# MCU.net
KiCad netlist of a schematic drawn in Altium Designer
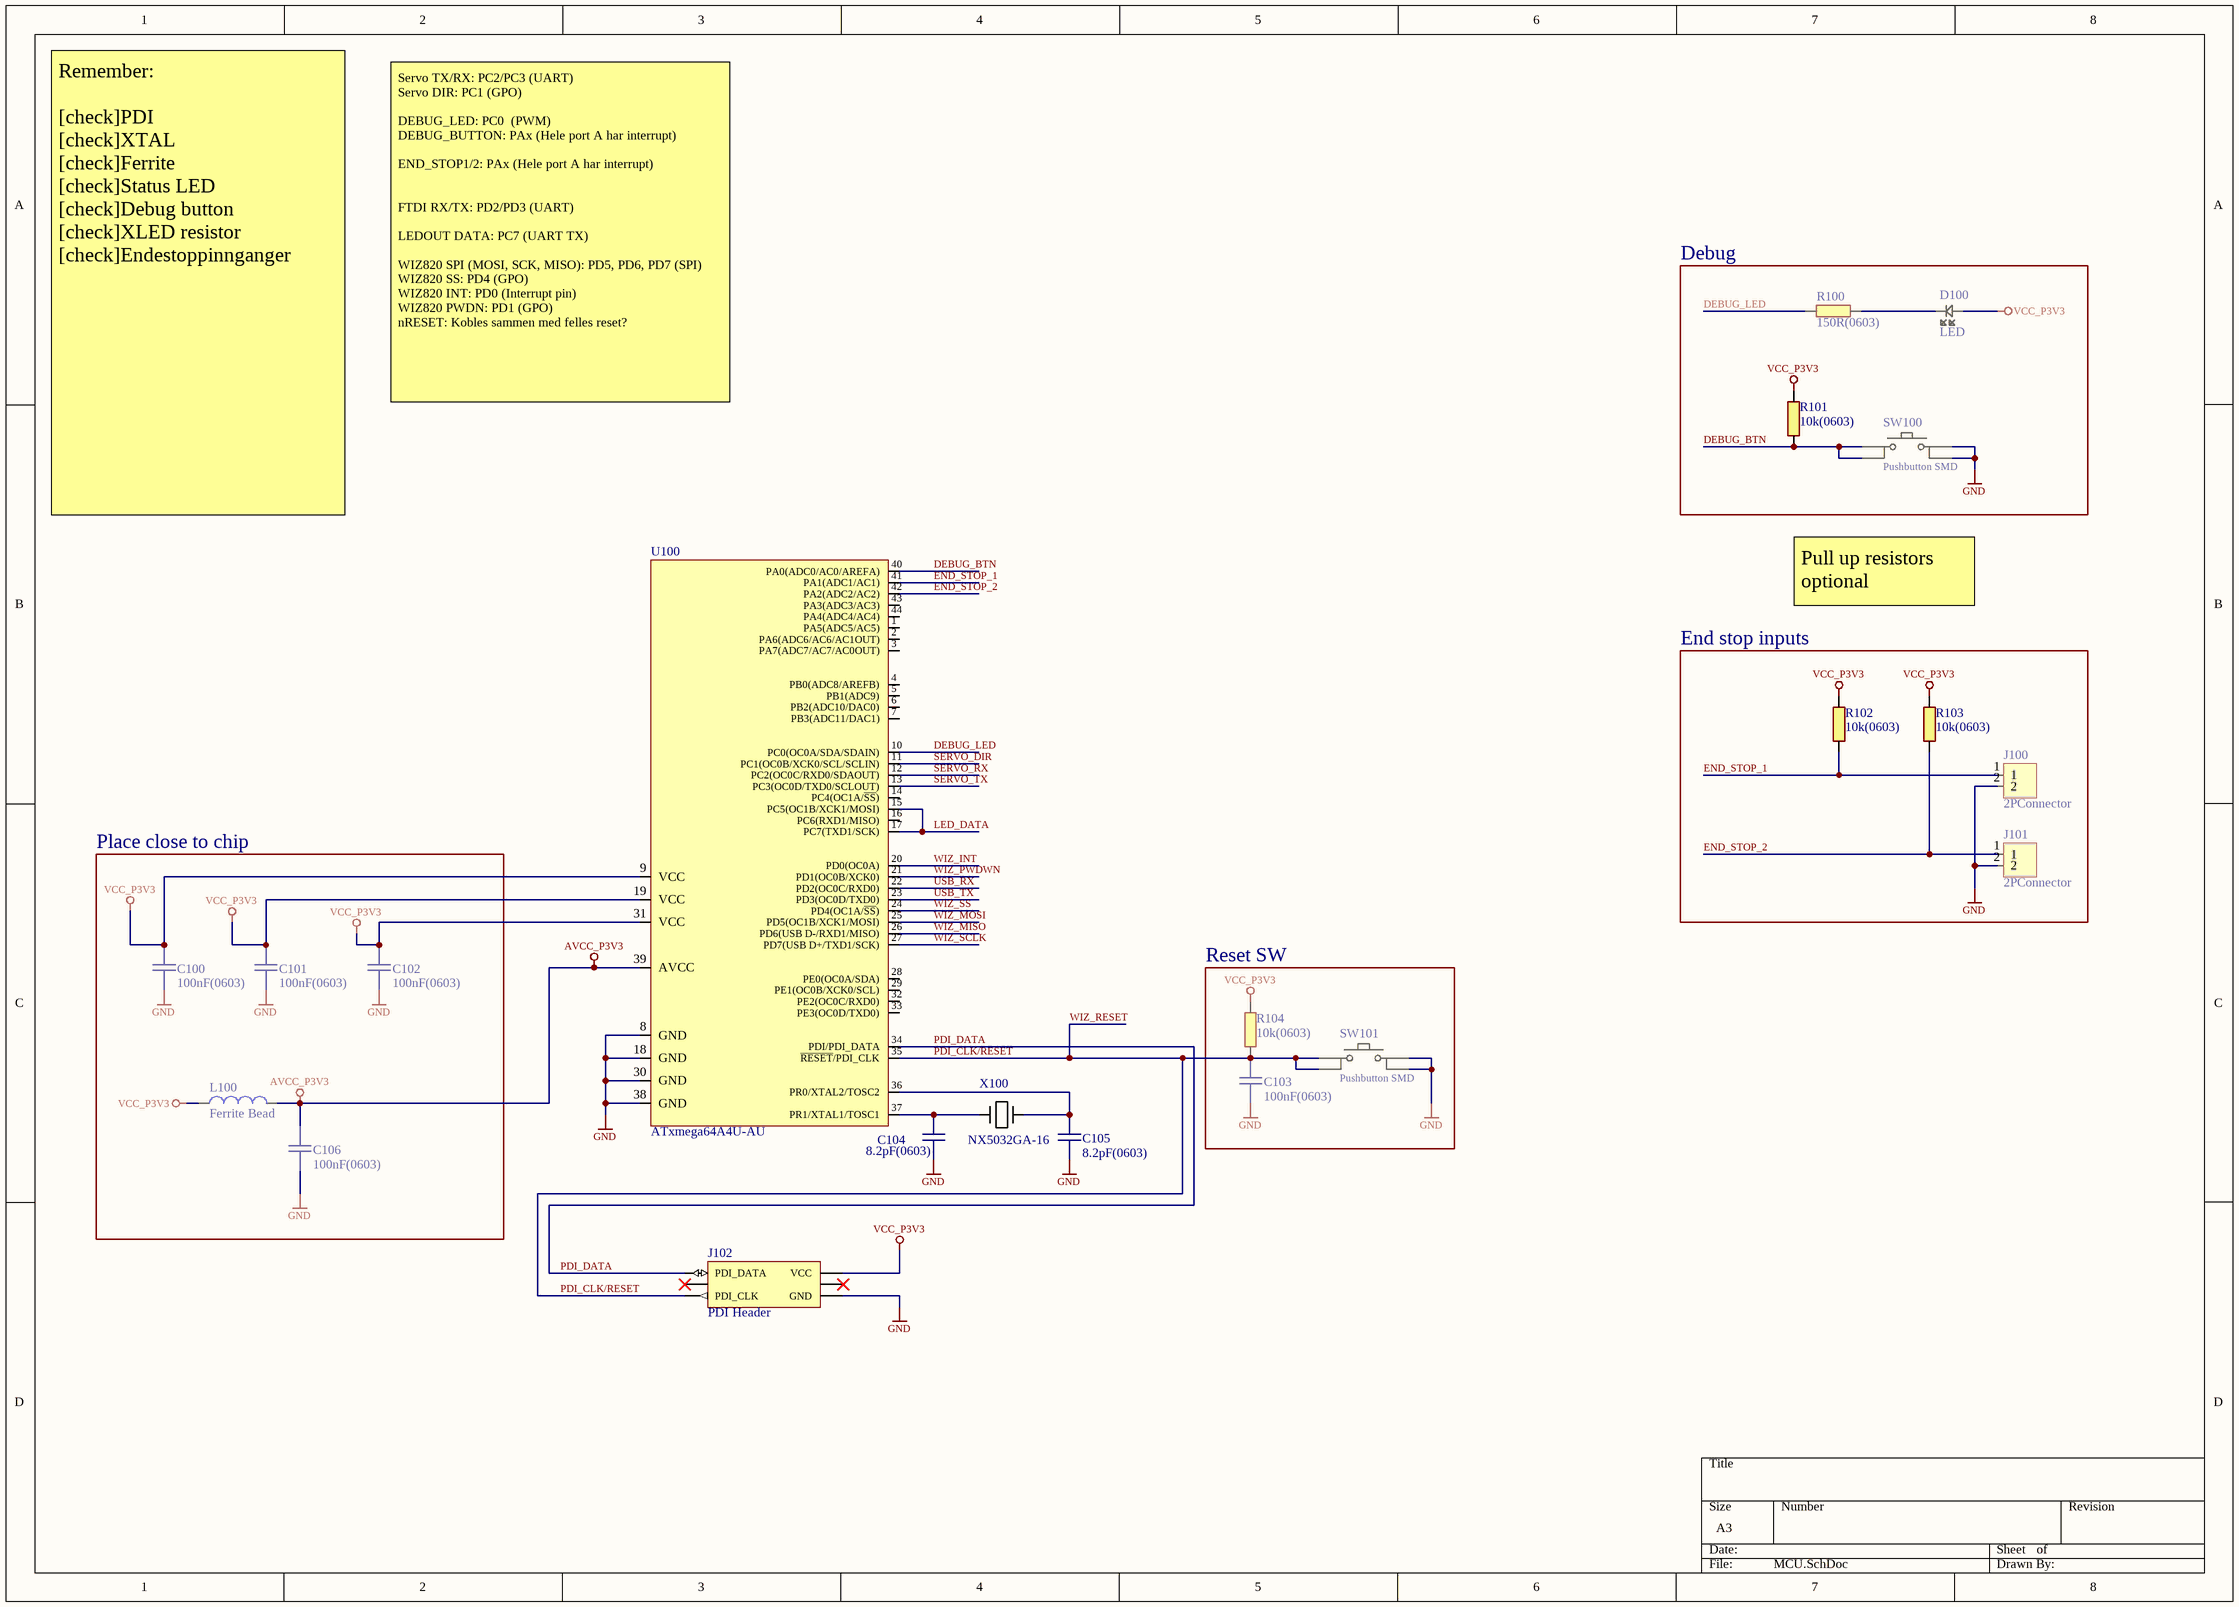
[diagram p0: MCU.SchDoc]

(export (version "E")
  (design (tool "Eeschema 10.0.6"))
  (components
    (comp (ref "C100")
      (value "100nF(0603)")
      (footprint "CAPC0603(1608)55_N")
      (description "100nF 0603 5% X7R 50V")
      (libsource (lib "OVLib") (part "CAP"))
    )
    (comp (ref "C101")
      (value "100nF(0603)")
      (footprint "CAPC0603(1608)55_N")
      (description "100nF 0603 5% X7R 50V")
      (libsource (lib "OVLib") (part "CAP"))
    )
    (comp (ref "C102")
      (value "100nF(0603)")
      (footprint "CAPC0603(1608)55_N")
      (description "100nF 0603 5% X7R 50V")
      (libsource (lib "OVLib") (part "CAP"))
    )
    (comp (ref "C103")
      (value "100nF(0603)")
      (footprint "CAPC0603(1608)55_N")
      (description "100nF 0603 5% X7R 50V")
      (libsource (lib "OVLib") (part "CAP"))
    )
    (comp (ref "C104")
      (value "8.2pF(0603)")
      (footprint "CAPC0603(1608)55_N")
      (description "0603 5% NP0 50V")
      (libsource (lib "OVLib") (part "CAP"))
    )
    (comp (ref "C105")
      (value "8.2pF(0603)")
      (footprint "CAPC0603(1608)55_N")
      (description "0603 5% NP0 50V")
      (libsource (lib "OVLib") (part "CAP"))
    )
    (comp (ref "C106")
      (value "100nF(0603)")
      (footprint "CAPC0603(1608)55_N")
      (description "100nF 0603 5% X7R 50V")
      (libsource (lib "OVLib") (part "CAP"))
    )
    (comp (ref "D100")
      (value "LED")
      (footprint "I_LEDC0603(1608)_N")
      (description "SMD")
      (libsource (lib "OVLib") (part "LED"))
    )
    (comp (ref "J100")
      (value "2PConnector")
      (footprint "JST_2P")
      (description "pris pr. stk.")
      (libsource (lib "OVLib") (part "2PConnector"))
    )
    (comp (ref "J101")
      (value "2PConnector")
      (footprint "JST_2P")
      (description "pris pr. stk.")
      (libsource (lib "OVLib") (part "2PConnector"))
    )
    (comp (ref "J102")
      (value "PDI Header")
      (footprint "HEADER_3x2")
      (description "PDI Xmega programming header")
      (libsource (lib "OVLib") (part "PDI-HEADER"))
    )
    (comp (ref "L100")
      (value "Ferrite Bead")
      (footprint "0603")
      (description "Ferrite Bead 0603")
      (fields (field (name "MPN") "BLM18SG331TN1D"))
      (libsource (lib "BLM18SG331TN1D") (part "BLM18SG331TN1D"))
    )
    (comp (ref "R100")
      (value "150R(0603)")
      (footprint "RESC0603(1608)_N")
      (description "0603 0.1W 1% Thick film resistor")
      (libsource (lib "") (part "Resistor2_1"))
    )
    (comp (ref "R101")
      (value "10k(0603)")
      (footprint "RESC0603(1608)_N")
      (description "10k 0603 0.1W 1% Thick film resistor")
      (libsource (lib "OVLib") (part "Resistor2"))
    )
    (comp (ref "R102")
      (value "10k(0603)")
      (footprint "RESC0603(1608)_N")
      (description "10k 0603 0.1W 1% Thick film resistor")
      (libsource (lib "OVLib") (part "Resistor2"))
    )
    (comp (ref "R103")
      (value "10k(0603)")
      (footprint "RESC0603(1608)_N")
      (description "10k 0603 0.1W 1% Thick film resistor")
      (libsource (lib "OVLib") (part "Resistor2"))
    )
    (comp (ref "R104")
      (value "10k(0603)")
      (footprint "RESC0603(1608)_N")
      (description "10k 0603 0.1W 1% Thick film resistor")
      (libsource (lib "OVLib") (part "Resistor2"))
    )
    (comp (ref "SW100")
      (value "Pushbutton SMD")
      (footprint "SOIC254P500X160-4")
      (description "Momentary tactile pushbutton SMD")
      (libsource (lib "OVLib") (part "Pushbutton"))
    )
    (comp (ref "SW101")
      (value "Pushbutton SMD")
      (footprint "SOIC254P500X160-4")
      (description "Momentary tactile pushbutton SMD")
      (libsource (lib "OVLib") (part "Pushbutton"))
    )
    (comp (ref "U100")
      (value "ATxmega64A4U-AU")
      (footprint "44A_N")
      (description "8/16-bit AVR XMEGA A4U Microcontroller, 1.6-3.6V, 64KB + 4KB Flash")
      (libsource (lib "ATxmega64A4U-AU") (part "ATxmega64A4U-AU"))
    )
    (comp (ref "X100")
      (value "NX5032GA-16")
      (footprint "CRYSTAL-ABM7")
      (description "Crystal 16 MHz")
      (libsource (lib "OVLib") (part "GENERIC-CRYSTAL"))
    )
  )
  (nets
    (net (code "1") (name "/DEBUG_BTN") (class "Default")
      (node (ref "R101") (pin "1") (pinfunction "1_1") (pintype "passive"))
      (node (ref "SW100") (pin "1") (pinfunction "1_1") (pintype "passive"))
      (node (ref "SW100") (pin "2") (pinfunction "2_2") (pintype "passive"))
      (node (ref "U100") (pin "40") (pinfunction "PA0(ADC0/AC0/AREFA)_40") (pintype "bidirectional"))
    )
    (net (code "2") (name "/DEBUG_LED") (class "Default")
      (node (ref "R100") (pin "1") (pinfunction "1_1") (pintype "passive"))
      (node (ref "U100") (pin "10") (pinfunction "PC0(OC0A/SDA/SDAIN)_10") (pintype "bidirectional"))
    )
    (net (code "3") (name "/END_STOP_1") (class "Default")
      (node (ref "J100") (pin "1") (pinfunction "1_1") (pintype "passive"))
      (node (ref "R102") (pin "1") (pinfunction "1_1") (pintype "passive"))
      (node (ref "U100") (pin "41") (pinfunction "PA1(ADC1/AC1)_41") (pintype "bidirectional"))
    )
    (net (code "4") (name "/END_STOP_2") (class "Default")
      (node (ref "J101") (pin "1") (pinfunction "1_1") (pintype "passive"))
      (node (ref "R103") (pin "1") (pinfunction "1_1") (pintype "passive"))
      (node (ref "U100") (pin "42") (pinfunction "PA2(ADC2/AC2)_42") (pintype "bidirectional"))
    )
    (net (code "5") (name "/LED_DATA") (class "Default")
      (node (ref "U100") (pin "15") (pinfunction "PC5(OC1B/XCK1/MOSI)_15") (pintype "bidirectional"))
      (node (ref "U100") (pin "17") (pinfunction "PC7(TXD1/SCK)_17") (pintype "bidirectional"))
    )
    (net (code "6") (name "/PDI_CLK{slash}RESET") (class "Default")
      (node (ref "C103") (pin "2") (pinfunction "2_2") (pintype "passive"))
      (node (ref "J102") (pin "5") (pinfunction "PDI_CLK_5") (pintype "output"))
      (node (ref "R104") (pin "1") (pinfunction "1_1") (pintype "passive"))
      (node (ref "SW101") (pin "1") (pinfunction "1_1") (pintype "passive"))
      (node (ref "SW101") (pin "2") (pinfunction "2_2") (pintype "passive"))
      (node (ref "U100") (pin "35") (pinfunction "~{RESET}/PDI_CLK_35") (pintype "input"))
    )
    (net (code "7") (name "/PDI_DATA") (class "Default")
      (node (ref "J102") (pin "1") (pinfunction "PDI_DATA_1") (pintype "bidirectional"))
      (node (ref "U100") (pin "34") (pinfunction "PDI/PDI_DATA_34") (pintype "bidirectional"))
    )
    (net (code "8") (name "/SERVO_DIR") (class "Default")
      (node (ref "U100") (pin "11") (pinfunction "PC1(OC0B/XCK0/SCL/SCLIN)_11") (pintype "bidirectional"))
    )
    (net (code "9") (name "/SERVO_RX") (class "Default")
      (node (ref "U100") (pin "12") (pinfunction "PC2(OC0C/RXD0/SDAOUT)_12") (pintype "bidirectional"))
    )
    (net (code "10") (name "/SERVO_TX") (class "Default")
      (node (ref "U100") (pin "13") (pinfunction "PC3(OC0D/TXD0/SCLOUT)_13") (pintype "bidirectional"))
    )
    (net (code "11") (name "/USB_RX") (class "Default")
      (node (ref "U100") (pin "22") (pinfunction "PD2(OC0C/RXD0)_22") (pintype "bidirectional"))
    )
    (net (code "12") (name "/USB_TX") (class "Default")
      (node (ref "U100") (pin "23") (pinfunction "PD3(OC0D/TXD0)_23") (pintype "bidirectional"))
    )
    (net (code "13") (name "/WIZ_INT") (class "Default")
      (node (ref "U100") (pin "20") (pinfunction "PD0(OC0A)_20") (pintype "bidirectional"))
    )
    (net (code "14") (name "/WIZ_MISO") (class "Default")
      (node (ref "U100") (pin "26") (pinfunction "PD6(USB_D-/RXD1/MISO)_26") (pintype "bidirectional"))
    )
    (net (code "15") (name "/WIZ_MOSI") (class "Default")
      (node (ref "U100") (pin "25") (pinfunction "PD5(OC1B/XCK1/MOSI)_25") (pintype "bidirectional"))
    )
    (net (code "16") (name "/WIZ_PWDWN") (class "Default")
      (node (ref "U100") (pin "21") (pinfunction "PD1(OC0B/XCK0)_21") (pintype "bidirectional"))
    )
    (net (code "17") (name "/WIZ_SCLK") (class "Default")
      (node (ref "U100") (pin "27") (pinfunction "PD7(USB_D+/TXD1/SCK)_27") (pintype "bidirectional"))
    )
    (net (code "18") (name "/WIZ_SS") (class "Default")
      (node (ref "U100") (pin "24") (pinfunction "PD4(OC1A/~{SS})_24") (pintype "bidirectional"))
    )
    (net (code "19") (name "AVCC_P3V3") (class "Default")
      (node (ref "C106") (pin "2") (pinfunction "2_2") (pintype "passive"))
      (node (ref "L100") (pin "2") (pintype "passive"))
      (node (ref "U100") (pin "39") (pinfunction "AVCC_39") (pintype "power_in"))
    )
    (net (code "20") (name "GND") (class "Default")
      (node (ref "C100") (pin "2") (pinfunction "2_2") (pintype "passive"))
      (node (ref "C101") (pin "2") (pinfunction "2_2") (pintype "passive"))
      (node (ref "C102") (pin "2") (pinfunction "2_2") (pintype "passive"))
      (node (ref "C103") (pin "1") (pinfunction "1_1") (pintype "passive"))
      (node (ref "C104") (pin "1") (pinfunction "1_1") (pintype "passive"))
      (node (ref "C105") (pin "1") (pinfunction "1_1") (pintype "passive"))
      (node (ref "C106") (pin "1") (pinfunction "1_1") (pintype "passive"))
      (node (ref "J100") (pin "2") (pinfunction "2_2") (pintype "passive"))
      (node (ref "J101") (pin "2") (pinfunction "2_2") (pintype "passive"))
      (node (ref "J102") (pin "6") (pinfunction "GND_6") (pintype "power_in"))
      (node (ref "SW100") (pin "3") (pinfunction "3_3") (pintype "passive"))
      (node (ref "SW100") (pin "4") (pinfunction "4_4") (pintype "passive"))
      (node (ref "SW101") (pin "3") (pinfunction "3_3") (pintype "passive"))
      (node (ref "SW101") (pin "4") (pinfunction "4_4") (pintype "passive"))
      (node (ref "U100") (pin "18") (pinfunction "GND_18") (pintype "power_in"))
      (node (ref "U100") (pin "30") (pinfunction "GND_30") (pintype "power_in"))
      (node (ref "U100") (pin "38") (pinfunction "GND_38") (pintype "power_in"))
      (node (ref "U100") (pin "8") (pinfunction "GND_8") (pintype "power_in"))
    )
    (net (code "21") (name "Net-(D100-Pad2)") (class "Default")
      (node (ref "D100") (pin "2") (pinfunction "2_2") (pintype "passive"))
      (node (ref "R100") (pin "2") (pinfunction "2_2") (pintype "passive"))
    )
    (net (code "22") (name "Net-(U100-PR0{slash}XTAL2{slash}TOSC2)") (class "Default")
      (node (ref "C105") (pin "2") (pinfunction "2_2") (pintype "passive"))
      (node (ref "U100") (pin "36") (pinfunction "PR0/XTAL2/TOSC2_36") (pintype "bidirectional"))
      (node (ref "X100") (pin "2") (pintype "passive"))
    )
    (net (code "23") (name "Net-(U100-PR1{slash}XTAL1{slash}TOSC1)") (class "Default")
      (node (ref "C104") (pin "2") (pinfunction "2_2") (pintype "passive"))
      (node (ref "U100") (pin "37") (pinfunction "PR1/XTAL1/TOSC1_37") (pintype "bidirectional"))
      (node (ref "X100") (pin "1") (pintype "passive"))
    )
    (net (code "24") (name "VCC_P3V3") (class "Default")
      (node (ref "C100") (pin "1") (pinfunction "1_1") (pintype "passive"))
      (node (ref "C101") (pin "1") (pinfunction "1_1") (pintype "passive"))
      (node (ref "C102") (pin "1") (pinfunction "1_1") (pintype "passive"))
      (node (ref "D100") (pin "1") (pinfunction "1_1") (pintype "passive"))
      (node (ref "J102") (pin "2") (pinfunction "VCC_2") (pintype "power_in"))
      (node (ref "L100") (pin "1") (pintype "passive"))
      (node (ref "R101") (pin "2") (pinfunction "2_2") (pintype "passive"))
      (node (ref "R102") (pin "2") (pinfunction "2_2") (pintype "passive"))
      (node (ref "R103") (pin "2") (pinfunction "2_2") (pintype "passive"))
      (node (ref "R104") (pin "2") (pinfunction "2_2") (pintype "passive"))
      (node (ref "U100") (pin "19") (pinfunction "VCC_19") (pintype "power_in"))
      (node (ref "U100") (pin "31") (pinfunction "VCC_31") (pintype "power_in"))
      (node (ref "U100") (pin "9") (pinfunction "VCC_9") (pintype "power_in"))
    )
    (net (code "25") (name "unconnected-(J102-Pad3)") (class "Default")
      (node (ref "J102") (pin "3") (pinfunction "3_3") (pintype "passive+no_connect"))
    )
    (net (code "26") (name "unconnected-(J102-Pad4)") (class "Default")
      (node (ref "J102") (pin "4") (pinfunction "4_4") (pintype "passive+no_connect"))
    )
    (net (code "27") (name "unconnected-(U100-PA3(ADC3{slash}AC3)-Pad43)") (class "Default")
      (node (ref "U100") (pin "43") (pinfunction "PA3(ADC3/AC3)_43") (pintype "bidirectional"))
    )
    (net (code "28") (name "unconnected-(U100-PA4(ADC4{slash}AC4)-Pad44)") (class "Default")
      (node (ref "U100") (pin "44") (pinfunction "PA4(ADC4/AC4)_44") (pintype "bidirectional"))
    )
    (net (code "29") (name "unconnected-(U100-PA5(ADC5{slash}AC5)-Pad1)") (class "Default")
      (node (ref "U100") (pin "1") (pinfunction "PA5(ADC5/AC5)_1") (pintype "bidirectional"))
    )
    (net (code "30") (name "unconnected-(U100-PA6(ADC6{slash}AC6{slash}AC1OUT)-Pad2)") (class "Default")
      (node (ref "U100") (pin "2") (pinfunction "PA6(ADC6/AC6/AC1OUT)_2") (pintype "bidirectional"))
    )
    (net (code "31") (name "unconnected-(U100-PA7(ADC7{slash}AC7{slash}AC0OUT)-Pad3)") (class "Default")
      (node (ref "U100") (pin "3") (pinfunction "PA7(ADC7/AC7/AC0OUT)_3") (pintype "bidirectional"))
    )
    (net (code "32") (name "unconnected-(U100-PB0(ADC8{slash}AREFB)-Pad4)") (class "Default")
      (node (ref "U100") (pin "4") (pinfunction "PB0(ADC8/AREFB)_4") (pintype "bidirectional"))
    )
    (net (code "33") (name "unconnected-(U100-PB1(ADC9)-Pad5)") (class "Default")
      (node (ref "U100") (pin "5") (pinfunction "PB1(ADC9)_5") (pintype "bidirectional"))
    )
    (net (code "34") (name "unconnected-(U100-PB2(ADC10{slash}DAC0)-Pad6)") (class "Default")
      (node (ref "U100") (pin "6") (pinfunction "PB2(ADC10/DAC0)_6") (pintype "bidirectional"))
    )
    (net (code "35") (name "unconnected-(U100-PB3(ADC11{slash}DAC1)-Pad7)") (class "Default")
      (node (ref "U100") (pin "7") (pinfunction "PB3(ADC11/DAC1)_7") (pintype "bidirectional"))
    )
    (net (code "36") (name "unconnected-(U100-PC4(OC1A{slash}~{SS})-Pad14)") (class "Default")
      (node (ref "U100") (pin "14") (pinfunction "PC4(OC1A/~{SS})_14") (pintype "bidirectional"))
    )
    (net (code "37") (name "unconnected-(U100-PC6(RXD1{slash}MISO)-Pad16)") (class "Default")
      (node (ref "U100") (pin "16") (pinfunction "PC6(RXD1/MISO)_16") (pintype "bidirectional"))
    )
    (net (code "38") (name "unconnected-(U100-PE0(OC0A{slash}SDA)-Pad28)") (class "Default")
      (node (ref "U100") (pin "28") (pinfunction "PE0(OC0A/SDA)_28") (pintype "bidirectional"))
    )
    (net (code "39") (name "unconnected-(U100-PE1(OC0B{slash}XCK0{slash}SCL)-Pad29)") (class "Default")
      (node (ref "U100") (pin "29") (pinfunction "PE1(OC0B/XCK0/SCL)_29") (pintype "bidirectional"))
    )
    (net (code "40") (name "unconnected-(U100-PE2(OC0C{slash}RXD0)-Pad32)") (class "Default")
      (node (ref "U100") (pin "32") (pinfunction "PE2(OC0C/RXD0)_32") (pintype "bidirectional"))
    )
    (net (code "41") (name "unconnected-(U100-PE3(OC0D{slash}TXD0)-Pad33)") (class "Default")
      (node (ref "U100") (pin "33") (pinfunction "PE3(OC0D/TXD0)_33") (pintype "bidirectional"))
    )
  )
)
